# peripherals.net
KiCad netlist of a schematic drawn in Altium Designer
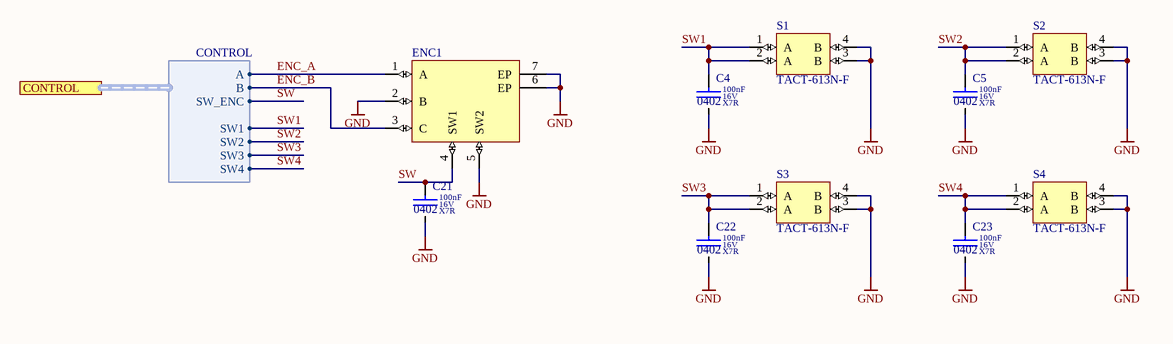
[diagram p0: peripherals.SchDoc]

(export (version "E")
  (design (tool "Eeschema 10.0.6"))
  (components
    (comp (ref "C4")
      (value "100nF")
      (footprint "C_0402_1005")
      (description "Capacitor")
      (fields
        (field (name "DIELECTRIC") "X7R")
        (field (name "VOLTAGE") "16V")
        (field (name "SCH_FOOTPRINT") "0402")
        (field (name "PART NUMBER") "C_100nF_16V_X7R_0402_10")
        (field (name "MANUFACTURER") "Murata")
      )
      (libsource (lib "Library") (part "C"))
    )
    (comp (ref "C5")
      (value "100nF")
      (footprint "C_0402_1005")
      (description "Capacitor")
      (fields
        (field (name "DIELECTRIC") "X7R")
        (field (name "VOLTAGE") "16V")
        (field (name "SCH_FOOTPRINT") "0402")
        (field (name "PART NUMBER") "C_100nF_16V_X7R_0402_10")
        (field (name "MANUFACTURER") "Murata")
      )
      (libsource (lib "Library") (part "C"))
    )
    (comp (ref "C21")
      (value "100nF")
      (footprint "C_0402_1005")
      (description "Capacitor")
      (fields
        (field (name "DIELECTRIC") "X7R")
        (field (name "VOLTAGE") "16V")
        (field (name "SCH_FOOTPRINT") "0402")
        (field (name "PART NUMBER") "C_100nF_16V_X7R_0402_10")
        (field (name "MANUFACTURER") "Murata")
      )
      (libsource (lib "Library") (part "C"))
    )
    (comp (ref "C22")
      (value "100nF")
      (footprint "C_0402_1005")
      (description "Capacitor")
      (fields
        (field (name "DIELECTRIC") "X7R")
        (field (name "VOLTAGE") "16V")
        (field (name "SCH_FOOTPRINT") "0402")
        (field (name "PART NUMBER") "C_100nF_16V_X7R_0402_10")
        (field (name "MANUFACTURER") "Murata")
      )
      (libsource (lib "Library") (part "C"))
    )
    (comp (ref "C23")
      (value "100nF")
      (footprint "C_0402_1005")
      (description "Capacitor")
      (fields
        (field (name "DIELECTRIC") "X7R")
        (field (name "VOLTAGE") "16V")
        (field (name "SCH_FOOTPRINT") "0402")
        (field (name "PART NUMBER") "C_100nF_16V_X7R_0402_10")
        (field (name "MANUFACTURER") "Murata")
      )
      (libsource (lib "Library") (part "C"))
    )
    (comp (ref "ENC1")
      (value "Wurth Elektronik 482016514001")
      (footprint "ENCODER")
      (libsource (lib "soldering_station") (part "ENCODER"))
    )
    (comp (ref "S1")
      (value "TACT-613N-F")
      (footprint "TACT-613N-F")
      (libsource (lib "soldering_station") (part "TACT-613N-F"))
    )
    (comp (ref "S2")
      (value "TACT-613N-F")
      (footprint "TACT-613N-F")
      (libsource (lib "soldering_station") (part "TACT-613N-F"))
    )
    (comp (ref "S3")
      (value "TACT-613N-F")
      (footprint "TACT-613N-F")
      (libsource (lib "soldering_station") (part "TACT-613N-F"))
    )
    (comp (ref "S4")
      (value "TACT-613N-F")
      (footprint "TACT-613N-F")
      (libsource (lib "soldering_station") (part "TACT-613N-F"))
    )
  )
  (nets
    (net (code "2") (name "/ENC_A") (class "Default")
      (node (ref "ENC1") (pin "1") (pinfunction "A_1") (pintype "bidirectional"))
    )
    (net (code "3") (name "/ENC_B") (class "Default")
      (node (ref "ENC1") (pin "3") (pinfunction "C_3") (pintype "bidirectional"))
    )
    (net (code "4") (name "/SW") (class "Default")
      (node (ref "C21") (pin "1") (pinfunction "1_1") (pintype "passive"))
      (node (ref "ENC1") (pin "4") (pinfunction "SW1_4") (pintype "bidirectional"))
    )
    (net (code "5") (name "/SW1") (class "Default")
      (node (ref "C4") (pin "1") (pinfunction "1_1") (pintype "passive"))
      (node (ref "S1") (pin "1") (pinfunction "A_1") (pintype "bidirectional"))
      (node (ref "S1") (pin "2") (pinfunction "A_2") (pintype "bidirectional"))
    )
    (net (code "6") (name "/SW2") (class "Default")
      (node (ref "C5") (pin "1") (pinfunction "1_1") (pintype "passive"))
      (node (ref "S2") (pin "1") (pinfunction "A_1") (pintype "bidirectional"))
      (node (ref "S2") (pin "2") (pinfunction "A_2") (pintype "bidirectional"))
    )
    (net (code "7") (name "/SW3") (class "Default")
      (node (ref "C22") (pin "1") (pinfunction "1_1") (pintype "passive"))
      (node (ref "S3") (pin "1") (pinfunction "A_1") (pintype "bidirectional"))
      (node (ref "S3") (pin "2") (pinfunction "A_2") (pintype "bidirectional"))
    )
    (net (code "8") (name "/SW4") (class "Default")
      (node (ref "C23") (pin "1") (pinfunction "1_1") (pintype "passive"))
      (node (ref "S4") (pin "1") (pinfunction "A_1") (pintype "bidirectional"))
      (node (ref "S4") (pin "2") (pinfunction "A_2") (pintype "bidirectional"))
    )
    (net (code "10") (name "GND") (class "Default")
      (node (ref "C21") (pin "2") (pinfunction "2_2") (pintype "passive"))
      (node (ref "C22") (pin "2") (pinfunction "2_2") (pintype "passive"))
      (node (ref "C23") (pin "2") (pinfunction "2_2") (pintype "passive"))
      (node (ref "C4") (pin "2") (pinfunction "2_2") (pintype "passive"))
      (node (ref "C5") (pin "2") (pinfunction "2_2") (pintype "passive"))
      (node (ref "ENC1") (pin "2") (pinfunction "B_2") (pintype "bidirectional"))
      (node (ref "ENC1") (pin "5") (pinfunction "SW2_5") (pintype "bidirectional"))
      (node (ref "ENC1") (pin "6") (pinfunction "EP_6") (pintype "passive"))
      (node (ref "ENC1") (pin "7") (pinfunction "EP_7") (pintype "passive"))
      (node (ref "S1") (pin "3") (pinfunction "B_3") (pintype "bidirectional"))
      (node (ref "S1") (pin "4") (pinfunction "B_4") (pintype "bidirectional"))
      (node (ref "S2") (pin "3") (pinfunction "B_3") (pintype "bidirectional"))
      (node (ref "S2") (pin "4") (pinfunction "B_4") (pintype "bidirectional"))
      (node (ref "S3") (pin "3") (pinfunction "B_3") (pintype "bidirectional"))
      (node (ref "S3") (pin "4") (pinfunction "B_4") (pintype "bidirectional"))
      (node (ref "S4") (pin "3") (pinfunction "B_3") (pintype "bidirectional"))
      (node (ref "S4") (pin "4") (pinfunction "B_4") (pintype "bidirectional"))
    )
  )
)
